# H2BR0-5.net
KiCad netlist of a schematic drawn in EAGLE
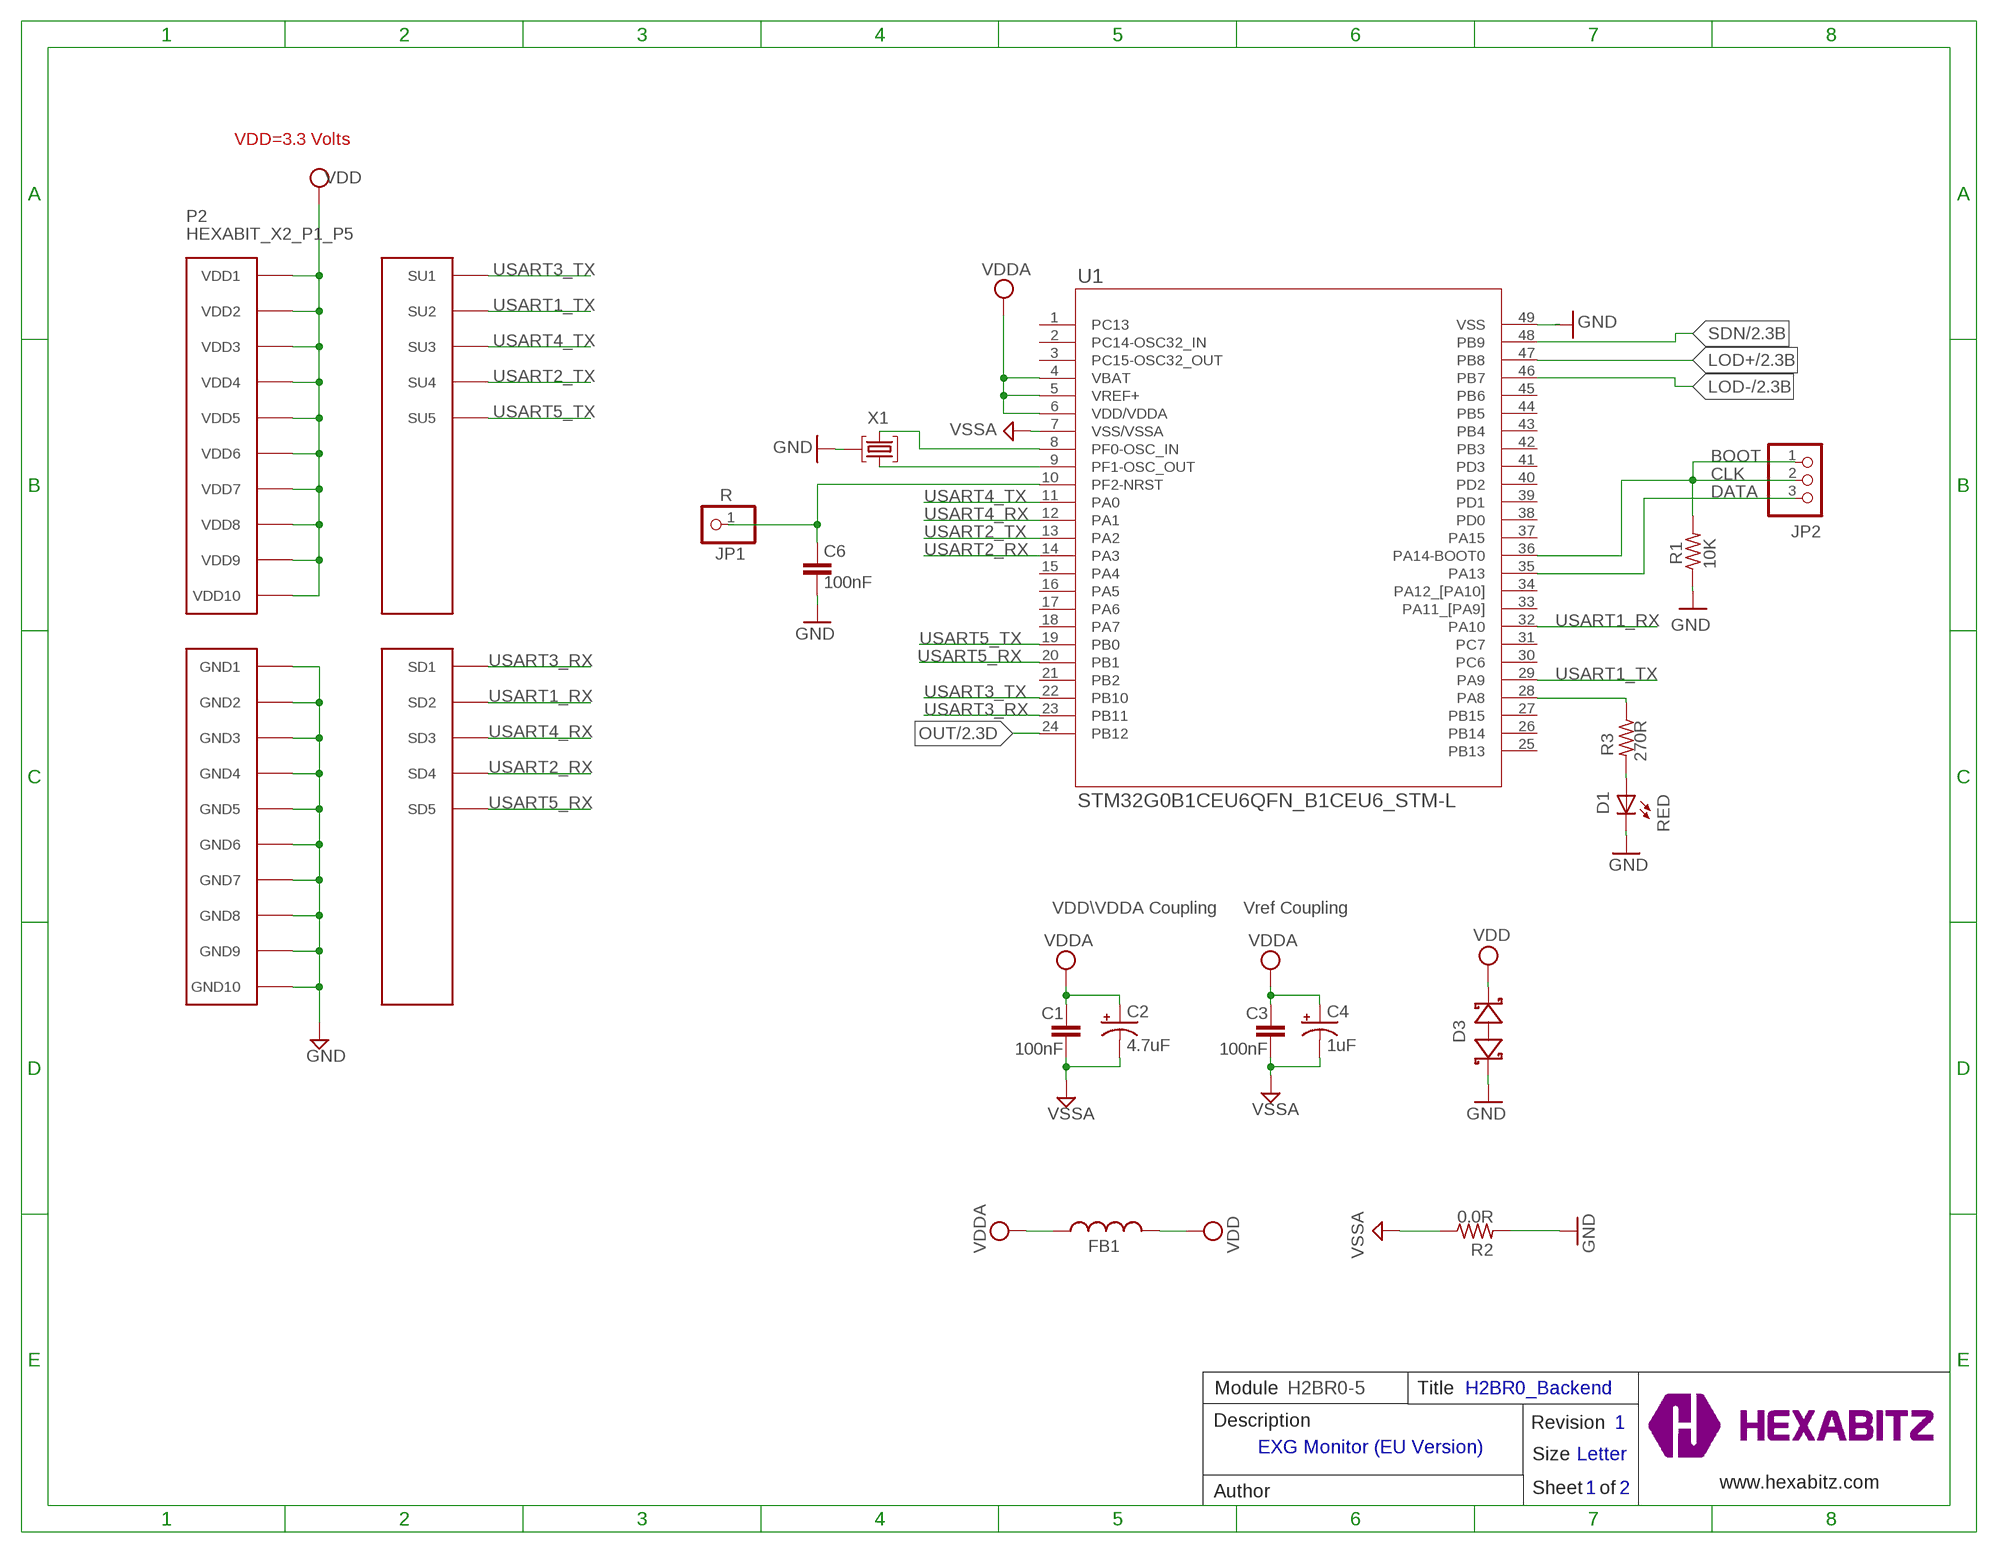
[diagram p0: schematic, sheet 1]
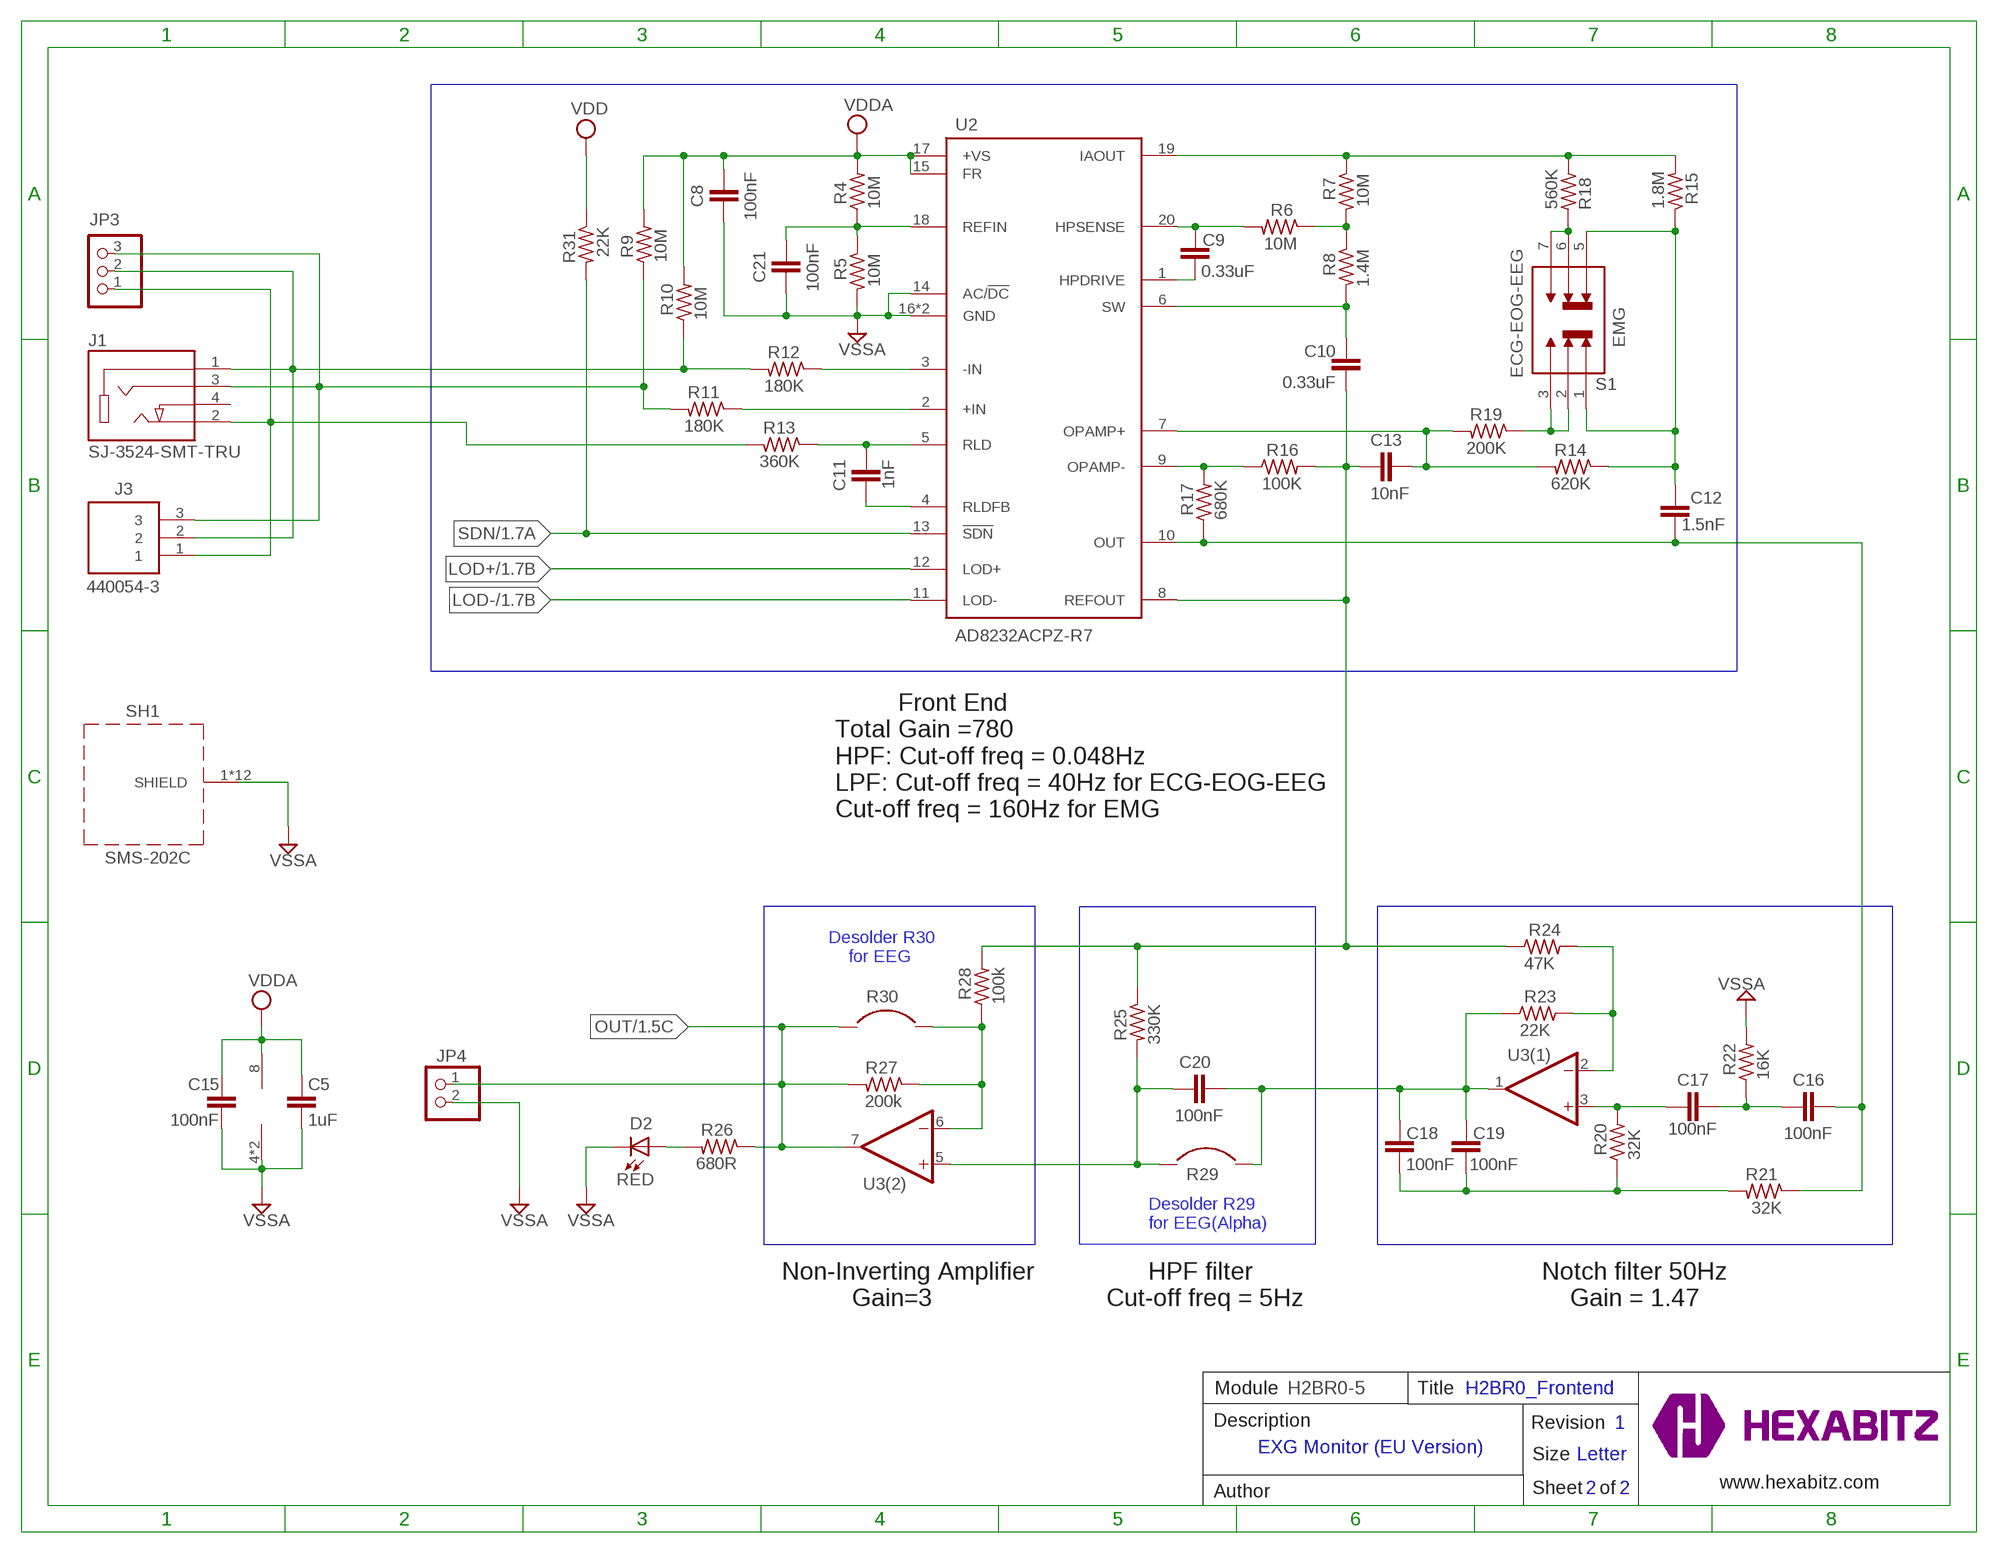
[diagram p1: schematic, sheet 2]

(export (version "E")
  (design (tool "Eeschema 10.0.6"))
  (components
    (comp (ref "C1")
      (value "100nF")
      (footprint "eagle-import:C-0603")
      (libsource (lib "eagle-import") (part "C-0603"))
    )
    (comp (ref "C2")
      (value "4.7uF")
      (footprint "eagle-import:C-0805-POL")
      (libsource (lib "eagle-import") (part "C-0805-POL"))
    )
    (comp (ref "C3")
      (value "100nF")
      (footprint "eagle-import:C-0603")
      (libsource (lib "eagle-import") (part "C-0603"))
    )
    (comp (ref "C4")
      (value "1uF")
      (footprint "eagle-import:C-0805-POL")
      (libsource (lib "eagle-import") (part "C-0805-POL"))
    )
    (comp (ref "C6")
      (value "100nF")
      (footprint "eagle-import:C-0603")
      (libsource (lib "eagle-import") (part "C-0603"))
    )
    (comp (ref "D1")
      (value "RED")
      (footprint "eagle-import:VLMS1300-GS08")
      (fields
        (field (name "MPN") "VLMS1300-GS08")
        (field (name "MFN") "Vishay")
        (field (name "MPN_1") "VLMS1300-GS08")
        (field (name "OCTOPART_URL") "https://octopart.com/vlms1300-gs08-vishay-21709201?r=sp&s=_gcP4_q8T1SC6PJQPTQ9yA")
      )
      (libsource (lib "eagle-import") (part "VLMS1300-GS08"))
    )
    (comp (ref "D3")
      (value "BOURNS_CDSOD323-T03SCBOURNS_CDSOD323-T03SC_0_0")
      (footprint "eagle-import:BOURNS_CDSOD323-T03SC_0")
      (fields (field (name "MPN") "CDSOD323-T03SC"))
      (libsource (lib "eagle-import") (part "BOURNS_CDSOD323-T03SCBOURNS_CDSOD323-T03SC_0_0"))
    )
    (comp (ref "FB1")
      (value "FB-0603")
      (footprint "eagle-import:FB-0603")
      (libsource (lib "eagle-import") (part "FB-0603"))
    )
    (comp (ref "JP1")
      (value "R")
      (footprint "eagle-import:1X01")
      (fields (field (name "MPN") "87227-1"))
      (libsource (lib "eagle-import") (part "PINHD-1X1"))
    )
    (comp (ref "JP2")
      (value "PINHD-1X3")
      (footprint "eagle-import:1X03")
      (libsource (lib "eagle-import") (part "PINHD-1X3"))
    )
    (comp (ref "P2")
      (value "HEXABIT_X2_P1_P5")
      (footprint "eagle-import:HEXABIT_17.32_X2_P1_P5")
      (libsource (lib "eagle-import") (part "HEXABIT_X2_P1_P5"))
    )
    (comp (ref "R1")
      (value "10K")
      (footprint "eagle-import:R-0603")
      (libsource (lib "eagle-import") (part "R-0603"))
    )
    (comp (ref "R2")
      (value "0.0R")
      (footprint "eagle-import:R-0603")
      (libsource (lib "eagle-import") (part "R-0603"))
    )
    (comp (ref "R3")
      (value "270R")
      (footprint "eagle-import:R-0603")
      (libsource (lib "eagle-import") (part "R-0603"))
    )
    (comp (ref "TRIMBLE-LOGO2")
      (value "HEXA-LOGO")
      (footprint "eagle-import:HEXA-LOGO")
      (libsource (lib "eagle-import") (part "HEXA-LOGO"))
    )
    (comp (ref "U1")
      (value "STM32G0B1CEU6QFN_B1CEU6_STM-L")
      (footprint "eagle-import:QFN_B1CEU6_STM-L")
      (fields
        (field (name "MANUFACTURER_PART_NUMBER") "STM32G0B1CEU6")
        (field (name "COPYRIGHT") "Copyright (C) 2021 Ultra Librarian. All rights reserved.")
      )
      (libsource (lib "eagle-import") (part "STM32G0B1CEU6QFN_B1CEU6_STM-L"))
    )
    (comp (ref "X1")
      (value "XTALL_CSTCE8M00G52")
      (footprint "eagle-import:XTALL_CSTCE8M00G52")
      (fields (field (name "MPN") "CSTCE8M00G52Z-R0"))
      (libsource (lib "eagle-import") (part "XTALL_CSTCE8M00G52"))
    )
    (comp (ref "C5")
      (value "1uF")
      (footprint "eagle-import:C-0402")
      (libsource (lib "eagle-import") (part "C-0402"))
    )
    (comp (ref "C8")
      (value "100nF")
      (footprint "eagle-import:C-0402")
      (libsource (lib "eagle-import") (part "C-0402"))
    )
    (comp (ref "C9")
      (value "0.33uF")
      (footprint "eagle-import:C-0402")
      (libsource (lib "eagle-import") (part "C-0402"))
    )
    (comp (ref "C10")
      (value "0.33uF")
      (footprint "eagle-import:C-0402")
      (libsource (lib "eagle-import") (part "C-0402"))
    )
    (comp (ref "C11")
      (value "1nF")
      (footprint "eagle-import:C-0402")
      (libsource (lib "eagle-import") (part "C-0402"))
    )
    (comp (ref "C12")
      (value "1.5nF")
      (footprint "eagle-import:C-0402")
      (libsource (lib "eagle-import") (part "C-0402"))
    )
    (comp (ref "C13")
      (value "10nF")
      (footprint "eagle-import:C-0402")
      (libsource (lib "eagle-import") (part "C-0402"))
    )
    (comp (ref "C15")
      (value "100nF")
      (footprint "eagle-import:C-0402")
      (libsource (lib "eagle-import") (part "C-0402"))
    )
    (comp (ref "C16")
      (value "100nF")
      (footprint "eagle-import:C-0402")
      (libsource (lib "eagle-import") (part "C-0402"))
    )
    (comp (ref "C17")
      (value "100nF")
      (footprint "eagle-import:C-0402")
      (libsource (lib "eagle-import") (part "C-0402"))
    )
    (comp (ref "C18")
      (value "100nF")
      (footprint "eagle-import:C-0402")
      (libsource (lib "eagle-import") (part "C-0402"))
    )
    (comp (ref "C19")
      (value "100nF")
      (footprint "eagle-import:C-0402")
      (libsource (lib "eagle-import") (part "C-0402"))
    )
    (comp (ref "C20")
      (value "100nF")
      (footprint "eagle-import:C-0402")
      (fields (field (name "MPN") "GRM188R61A105KA61J"))
      (libsource (lib "eagle-import") (part "C-0402"))
    )
    (comp (ref "C21")
      (value "100nF")
      (footprint "eagle-import:C-0402")
      (libsource (lib "eagle-import") (part "C-0402"))
    )
    (comp (ref "D2")
      (value "RED")
      (footprint "eagle-import:VLMS1300-GS08")
      (fields
        (field (name "MPN") "VLMS1300-GS08")
        (field (name "MFN") "Vishay")
        (field (name "MPN_1") "VLMS1300-GS08")
        (field (name "OCTOPART_URL") "https://octopart.com/vlms1300-gs08-vishay-21709201?r=sp&s=_gcP4_q8T1SC6PJQPTQ9yA")
      )
      (libsource (lib "eagle-import") (part "VLMS1300-GS08"))
    )
    (comp (ref "J1")
      (value "SJ-3524-SMT-TRU")
      (footprint "eagle-import:CUI_SJ-3524-SMT")
      (fields (field (name "MPN") "SJ-3524-SMT-TR"))
      (libsource (lib "eagle-import") (part "SJ-3524-SMT-TRU"))
    )
    (comp (ref "J3")
      (value "440054-3")
      (footprint "eagle-import:SHDR3W50P0X200_1X3_800X470X635")
      (fields (field (name "MOUSER_PART_NUMBER") "571-440054-3"))
      (libsource (lib "eagle-import") (part "440054-3"))
    )
    (comp (ref "JP3")
      (value "PINHD-1X3")
      (footprint "eagle-import:1X03")
      (libsource (lib "eagle-import") (part "PINHD-1X3"))
    )
    (comp (ref "JP4")
      (value "PINHD-1X2(ROUND)")
      (footprint "eagle-import:1X02")
      (libsource (lib "eagle-import") (part "PINHD-1X2(ROUND)"))
    )
    (comp (ref "R4")
      (value "10M")
      (footprint "eagle-import:R-0402")
      (libsource (lib "eagle-import") (part "R-0402"))
    )
    (comp (ref "R5")
      (value "10M")
      (footprint "eagle-import:R-0402")
      (libsource (lib "eagle-import") (part "R-0402"))
    )
    (comp (ref "R6")
      (value "10M")
      (footprint "eagle-import:R-0402")
      (libsource (lib "eagle-import") (part "R-0402"))
    )
    (comp (ref "R7")
      (value "10M")
      (footprint "eagle-import:R-0402")
      (libsource (lib "eagle-import") (part "R-0402"))
    )
    (comp (ref "R8")
      (value "1.4M")
      (footprint "eagle-import:R-0402")
      (libsource (lib "eagle-import") (part "R-0402"))
    )
    (comp (ref "R9")
      (value "10M")
      (footprint "eagle-import:R-0402")
      (libsource (lib "eagle-import") (part "R-0402"))
    )
    (comp (ref "R10")
      (value "10M")
      (footprint "eagle-import:R-0402")
      (libsource (lib "eagle-import") (part "R-0402"))
    )
    (comp (ref "R11")
      (value "180K")
      (footprint "eagle-import:R-0402")
      (libsource (lib "eagle-import") (part "R-0402"))
    )
    (comp (ref "R12")
      (value "180K")
      (footprint "eagle-import:R-0402")
      (libsource (lib "eagle-import") (part "R-0402"))
    )
    (comp (ref "R13")
      (value "360K")
      (footprint "eagle-import:R-0402")
      (libsource (lib "eagle-import") (part "R-0402"))
    )
    (comp (ref "R14")
      (value "620K")
      (footprint "eagle-import:R-0402")
      (libsource (lib "eagle-import") (part "R-0402"))
    )
    (comp (ref "R15")
      (value "1.8M")
      (footprint "eagle-import:R-0402")
      (libsource (lib "eagle-import") (part "R-0402"))
    )
    (comp (ref "R16")
      (value "100K")
      (footprint "eagle-import:R-0402")
      (libsource (lib "eagle-import") (part "R-0402"))
    )
    (comp (ref "R17")
      (value "680K")
      (footprint "eagle-import:R-0402")
      (libsource (lib "eagle-import") (part "R-0402"))
    )
    (comp (ref "R18")
      (value "560K")
      (footprint "eagle-import:R-0402")
      (libsource (lib "eagle-import") (part "R-0402"))
    )
    (comp (ref "R19")
      (value "200K")
      (footprint "eagle-import:R-0402")
      (libsource (lib "eagle-import") (part "R-0402"))
    )
    (comp (ref "R20")
      (value "32K")
      (footprint "eagle-import:R-0402")
      (libsource (lib "eagle-import") (part "R-0402"))
    )
    (comp (ref "R21")
      (value "32K")
      (footprint "eagle-import:R-0402")
      (libsource (lib "eagle-import") (part "R-0402"))
    )
    (comp (ref "R22")
      (value "16K")
      (footprint "eagle-import:R-0402")
      (libsource (lib "eagle-import") (part "R-0402"))
    )
    (comp (ref "R23")
      (value "22K")
      (footprint "eagle-import:R-0402")
      (libsource (lib "eagle-import") (part "R-0402"))
    )
    (comp (ref "R24")
      (value "47K")
      (footprint "eagle-import:R-0402")
      (libsource (lib "eagle-import") (part "R-0402"))
    )
    (comp (ref "R25")
      (value "330K")
      (footprint "eagle-import:R-0402")
      (libsource (lib "eagle-import") (part "R-0402"))
    )
    (comp (ref "R26")
      (value "680R")
      (footprint "eagle-import:R-0603")
      (libsource (lib "eagle-import") (part "R-0603"))
    )
    (comp (ref "R27")
      (value "200k")
      (footprint "eagle-import:R-0402")
      (libsource (lib "eagle-import") (part "R-0402"))
    )
    (comp (ref "R28")
      (value "100k")
      (footprint "eagle-import:R-0402")
      (libsource (lib "eagle-import") (part "R-0402"))
    )
    (comp (ref "R29")
      (value "SB-0603")
      (footprint "eagle-import:SB-0603")
      (libsource (lib "eagle-import") (part "SB-0603"))
    )
    (comp (ref "R30")
      (value "SB-0603")
      (footprint "eagle-import:SB-0603")
      (libsource (lib "eagle-import") (part "SB-0603"))
    )
    (comp (ref "R31")
      (value "22K")
      (footprint "eagle-import:R-0402")
      (libsource (lib "eagle-import") (part "R-0402"))
    )
    (comp (ref "S1")
      (value "JS202011JCQN")
      (footprint "eagle-import:SW_JS202011JCQN")
      (fields (field (name "MF") "C&K"))
      (libsource (lib "eagle-import") (part "JS202011JCQN"))
    )
    (comp (ref "SH1")
      (value "SMS-202C")
      (footprint "eagle-import:SMS202F")
      (fields (field (name "MOUSER_PART_NUMBER") "861-SMS-202C"))
      (libsource (lib "eagle-import") (part "SMS-202C"))
    )
    (comp (ref "U2")
      (value "AD8232ACPZ-R7")
      (footprint "eagle-import:QFN50P400X400X80-21N")
      (fields (field (name "MOUSER_PART_NUMBER") "584-AD8232ACPZ-R7"))
      (libsource (lib "eagle-import") (part "AD8232ACPZ-R7"))
    )
    (comp (ref "U3")
      (value "TSV772IQ2T_SEPARATED_SYMBOLSSON50P200X200X60-9N")
      (footprint "eagle-import:SON50P200X200X60-9N")
      (libsource (lib "eagle-import") (part "TSV772IQ2T_SEPARATED_SYMBOLSSON50P200X200X60-9N"))
    )
  )
  (nets
    (net (code "1") (name "CLK") (class "Default")
      (node (ref "JP2") (pin "1") (pinfunction "1_1") (pintype "passive"))
      (node (ref "JP2") (pin "2") (pinfunction "2_2") (pintype "passive"))
      (node (ref "R1") (pin "2") (pinfunction "2_2") (pintype "passive"))
      (node (ref "U1") (pin "36") (pinfunction "PA14-BOOT0_36") (pintype "bidirectional"))
    )
    (net (code "2") (name "DATA") (class "Default")
      (node (ref "JP2") (pin "3") (pinfunction "3_3") (pintype "passive"))
      (node (ref "U1") (pin "35") (pinfunction "PA13_35") (pintype "bidirectional"))
    )
    (net (code "3") (name "GND") (class "Default")
      (node (ref "C6") (pin "2") (pinfunction "2_2") (pintype "passive"))
      (node (ref "D1") (pin "C") (pinfunction "C_C") (pintype "passive"))
      (node (ref "D3") (pin "1") (pinfunction "A_1") (pintype "passive"))
      (node (ref "P2") (pin "PAD_PD11") (pinfunction "GND1_PAD_PD11") (pintype "power_in"))
      (node (ref "P2") (pin "PAD_PD12") (pinfunction "GND2_PAD_PD12") (pintype "power_in"))
      (node (ref "P2") (pin "PAD_PD13") (pinfunction "GND3_PAD_PD13") (pintype "power_in"))
      (node (ref "P2") (pin "PAD_PD14") (pinfunction "GND4_PAD_PD14") (pintype "power_in"))
      (node (ref "P2") (pin "PAD_PD15") (pinfunction "GND5_PAD_PD15") (pintype "power_in"))
      (node (ref "P2") (pin "PAD_PD16") (pinfunction "GND6_PAD_PD16") (pintype "power_in"))
      (node (ref "P2") (pin "PAD_PD17") (pinfunction "GND7_PAD_PD17") (pintype "power_in"))
      (node (ref "P2") (pin "PAD_PD18") (pinfunction "GND8_PAD_PD18") (pintype "power_in"))
      (node (ref "P2") (pin "PAD_PD19") (pinfunction "GND9_PAD_PD19") (pintype "power_in"))
      (node (ref "P2") (pin "PAD_PD20") (pinfunction "GND10_PAD_PD20") (pintype "power_in"))
      (node (ref "R1") (pin "1") (pinfunction "1_1") (pintype "passive"))
      (node (ref "R2") (pin "2") (pinfunction "2_2") (pintype "passive"))
      (node (ref "U1") (pin "49") (pinfunction "VSS_49") (pintype "passive"))
      (node (ref "X1") (pin "P$2") (pinfunction "2_P$2") (pintype "passive"))
    )
    (net (code "4") (name "LOD+") (class "Default")
      (node (ref "U1") (pin "47") (pinfunction "PB8_47") (pintype "bidirectional"))
      (node (ref "U2") (pin "12") (pinfunction "LOD+_12") (pintype "bidirectional"))
    )
    (net (code "5") (name "LOD-") (class "Default")
      (node (ref "U1") (pin "46") (pinfunction "PB7_46") (pintype "bidirectional"))
      (node (ref "U2") (pin "11") (pinfunction "LOD-_11") (pintype "bidirectional"))
    )
    (net (code "6") (name "Net-(C12-Pad2)") (class "Default")
      (node (ref "C12") (pin "2") (pinfunction "2_2") (pintype "passive"))
      (node (ref "R14") (pin "1") (pinfunction "1_1") (pintype "passive"))
      (node (ref "R15") (pin "1") (pinfunction "1_1") (pintype "passive"))
      (node (ref "S1") (pin "1") (pinfunction "1_1") (pintype "passive"))
      (node (ref "S1") (pin "5") (pinfunction "5_5") (pintype "passive"))
    )
    (net (code "7") (name "Net-(C16-Pad1)") (class "Default")
      (node (ref "C16") (pin "1") (pinfunction "1_1") (pintype "passive"))
      (node (ref "C17") (pin "2") (pinfunction "2_2") (pintype "passive"))
      (node (ref "R22") (pin "1") (pinfunction "1_1") (pintype "passive"))
    )
    (net (code "8") (name "Net-(C18-Pad1)") (class "Default")
      (node (ref "C18") (pin "1") (pinfunction "1_1") (pintype "passive"))
      (node (ref "C19") (pin "1") (pinfunction "1_1") (pintype "passive"))
      (node (ref "R20") (pin "1") (pinfunction "1_1") (pintype "passive"))
      (node (ref "R21") (pin "2") (pinfunction "2_2") (pintype "passive"))
    )
    (net (code "9") (name "Net-(D1-PadA)") (class "Default")
      (node (ref "D1") (pin "A") (pinfunction "A_A") (pintype "passive"))
      (node (ref "R3") (pin "2") (pinfunction "2_2") (pintype "passive"))
    )
    (net (code "10") (name "Net-(D2-PadA)") (class "Default")
      (node (ref "D2") (pin "A") (pinfunction "A_A") (pintype "passive"))
      (node (ref "R26") (pin "2") (pinfunction "2_2") (pintype "passive"))
    )
    (net (code "11") (name "Net-(J1-Pad1)") (class "Default")
      (node (ref "J1") (pin "1") (pinfunction "1_1") (pintype "passive"))
      (node (ref "J3") (pin "2") (pinfunction "2_2") (pintype "bidirectional"))
      (node (ref "JP3") (pin "2") (pinfunction "2_2") (pintype "passive"))
      (node (ref "R10") (pin "1") (pinfunction "1_1") (pintype "passive"))
      (node (ref "R12") (pin "2") (pinfunction "2_2") (pintype "passive"))
    )
    (net (code "12") (name "Net-(J1-Pad2)") (class "Default")
      (node (ref "J1") (pin "2") (pinfunction "2_2") (pintype "passive"))
      (node (ref "J3") (pin "1") (pinfunction "1_1") (pintype "bidirectional"))
      (node (ref "JP3") (pin "1") (pinfunction "1_1") (pintype "passive"))
      (node (ref "R13") (pin "2") (pinfunction "2_2") (pintype "passive"))
    )
    (net (code "13") (name "Net-(J1-Pad3)") (class "Default")
      (node (ref "J1") (pin "3") (pinfunction "3_3") (pintype "passive"))
      (node (ref "J3") (pin "3") (pinfunction "3_3") (pintype "bidirectional"))
      (node (ref "JP3") (pin "3") (pinfunction "3_3") (pintype "passive"))
      (node (ref "R11") (pin "2") (pinfunction "2_2") (pintype "passive"))
      (node (ref "R9") (pin "1") (pinfunction "1_1") (pintype "passive"))
    )
    (net (code "14") (name "Net-(R6-Pad1)") (class "Default")
      (node (ref "R6") (pin "1") (pinfunction "1_1") (pintype "passive"))
      (node (ref "R7") (pin "2") (pinfunction "2_2") (pintype "passive"))
      (node (ref "R8") (pin "1") (pinfunction "1_1") (pintype "passive"))
    )
    (net (code "15") (name "Net-(R18-Pad2)") (class "Default")
      (node (ref "R18") (pin "2") (pinfunction "2_2") (pintype "passive"))
      (node (ref "S1") (pin "6") (pinfunction "6_6") (pintype "passive"))
      (node (ref "S1") (pin "7") (pinfunction "7_7") (pintype "passive"))
    )
    (net (code "16") (name "Net-(R19-Pad1)") (class "Default")
      (node (ref "R19") (pin "1") (pinfunction "1_1") (pintype "passive"))
      (node (ref "S1") (pin "2") (pinfunction "2_2") (pintype "passive"))
      (node (ref "S1") (pin "3") (pinfunction "3_3") (pintype "passive"))
    )
    (net (code "17") (name "Net-(U1-PA8)") (class "Default")
      (node (ref "R3") (pin "1") (pinfunction "1_1") (pintype "passive"))
      (node (ref "U1") (pin "28") (pinfunction "PA8_28") (pintype "bidirectional"))
    )
    (net (code "18") (name "Net-(U1-PF0-OSC_IN)") (class "Default")
      (node (ref "U1") (pin "8") (pinfunction "PF0-OSC_IN_8") (pintype "bidirectional"))
      (node (ref "X1") (pin "P$3") (pinfunction "3_P$3") (pintype "passive"))
    )
    (net (code "19") (name "Net-(U1-PF1-OSC_OUT)") (class "Default")
      (node (ref "U1") (pin "9") (pinfunction "PF1-OSC_OUT_9") (pintype "output"))
      (node (ref "X1") (pin "P$1") (pinfunction "1_P$1") (pintype "passive"))
    )
    (net (code "20") (name "Net-(U1-PF2-NRST)") (class "Default")
      (node (ref "C6") (pin "1") (pinfunction "1_1") (pintype "passive"))
      (node (ref "JP1") (pin "1") (pinfunction "1_1") (pintype "passive"))
      (node (ref "U1") (pin "10") (pinfunction "PF2-NRST_10") (pintype "bidirectional"))
    )
    (net (code "21") (name "Net-(U2-+IN)") (class "Default")
      (node (ref "R11") (pin "1") (pinfunction "1_1") (pintype "passive"))
      (node (ref "U2") (pin "2") (pinfunction "+IN_2") (pintype "bidirectional"))
    )
    (net (code "22") (name "Net-(U2--IN)") (class "Default")
      (node (ref "R12") (pin "1") (pinfunction "1_1") (pintype "passive"))
      (node (ref "U2") (pin "3") (pinfunction "-IN_3") (pintype "bidirectional"))
    )
    (net (code "23") (name "Net-(U2-HPDRIVE)") (class "Default")
      (node (ref "C9") (pin "2") (pinfunction "2_2") (pintype "passive"))
      (node (ref "U2") (pin "1") (pinfunction "HPDRIVE_1") (pintype "bidirectional"))
    )
    (net (code "24") (name "Net-(U2-HPSENSE)") (class "Default")
      (node (ref "C9") (pin "1") (pinfunction "1_1") (pintype "passive"))
      (node (ref "R6") (pin "2") (pinfunction "2_2") (pintype "passive"))
      (node (ref "U2") (pin "20") (pinfunction "HPSENSE_20") (pintype "bidirectional"))
    )
    (net (code "25") (name "Net-(U2-IAOUT)") (class "Default")
      (node (ref "R15") (pin "2") (pinfunction "2_2") (pintype "passive"))
      (node (ref "R18") (pin "1") (pinfunction "1_1") (pintype "passive"))
      (node (ref "R7") (pin "1") (pinfunction "1_1") (pintype "passive"))
      (node (ref "U2") (pin "19") (pinfunction "IAOUT_19") (pintype "bidirectional"))
    )
    (net (code "26") (name "Net-(U2-OPAMP+)") (class "Default")
      (node (ref "C13") (pin "1") (pinfunction "1_1") (pintype "passive"))
      (node (ref "R14") (pin "2") (pinfunction "2_2") (pintype "passive"))
      (node (ref "R19") (pin "2") (pinfunction "2_2") (pintype "passive"))
      (node (ref "U2") (pin "7") (pinfunction "OPAMP+_7") (pintype "bidirectional"))
    )
    (net (code "27") (name "Net-(U2-OPAMP-)") (class "Default")
      (node (ref "R16") (pin "1") (pinfunction "1_1") (pintype "passive"))
      (node (ref "R17") (pin "2") (pinfunction "2_2") (pintype "passive"))
      (node (ref "U2") (pin "9") (pinfunction "OPAMP-_9") (pintype "bidirectional"))
    )
    (net (code "28") (name "Net-(U2-OUT)") (class "Default")
      (node (ref "C12") (pin "1") (pinfunction "1_1") (pintype "passive"))
      (node (ref "C16") (pin "2") (pinfunction "2_2") (pintype "passive"))
      (node (ref "R17") (pin "1") (pinfunction "1_1") (pintype "passive"))
      (node (ref "R21") (pin "1") (pinfunction "1_1") (pintype "passive"))
      (node (ref "U2") (pin "10") (pinfunction "OUT_10") (pintype "bidirectional"))
    )
    (net (code "29") (name "Net-(U2-REFIN)") (class "Default")
      (node (ref "C21") (pin "1") (pinfunction "1_1") (pintype "passive"))
      (node (ref "R4") (pin "1") (pinfunction "1_1") (pintype "passive"))
      (node (ref "R5") (pin "1") (pinfunction "1_1") (pintype "passive"))
      (node (ref "U2") (pin "18") (pinfunction "REFIN_18") (pintype "bidirectional"))
    )
    (net (code "30") (name "Net-(U2-REFOUT)") (class "Default")
      (node (ref "C10") (pin "2") (pinfunction "2_2") (pintype "passive"))
      (node (ref "C13") (pin "2") (pinfunction "2_2") (pintype "passive"))
      (node (ref "R16") (pin "2") (pinfunction "2_2") (pintype "passive"))
      (node (ref "R24") (pin "1") (pinfunction "1_1") (pintype "passive"))
      (node (ref "R25") (pin "1") (pinfunction "1_1") (pintype "passive"))
      (node (ref "R28") (pin "2") (pinfunction "2_2") (pintype "passive"))
      (node (ref "U2") (pin "8") (pinfunction "REFOUT_8") (pintype "bidirectional"))
    )
    (net (code "31") (name "Net-(U2-RLD)") (class "Default")
      (node (ref "C11") (pin "1") (pinfunction "1_1") (pintype "passive"))
      (node (ref "R13") (pin "1") (pinfunction "1_1") (pintype "passive"))
      (node (ref "U2") (pin "5") (pinfunction "RLD_5") (pintype "bidirectional"))
    )
    (net (code "32") (name "Net-(U2-RLDFB)") (class "Default")
      (node (ref "C11") (pin "2") (pinfunction "2_2") (pintype "passive"))
      (node (ref "U2") (pin "4") (pinfunction "RLDFB_4") (pintype "bidirectional"))
    )
    (net (code "33") (name "Net-(U2-SW)") (class "Default")
      (node (ref "C10") (pin "1") (pinfunction "1_1") (pintype "passive"))
      (node (ref "R8") (pin "2") (pinfunction "2_2") (pintype "passive"))
      (node (ref "U2") (pin "6") (pinfunction "SW_6") (pintype "bidirectional"))
    )
    (net (code "34") (name "Net-(U3A-+IN)") (class "Default")
      (node (ref "C17") (pin "1") (pinfunction "1_1") (pintype "passive"))
      (node (ref "R20") (pin "2") (pinfunction "2_2") (pintype "passive"))
      (node (ref "U3") (pin "3") (pinfunction "+IN_3") (pintype "input"))
    )
    (net (code "35") (name "Net-(U3A--IN)") (class "Default")
      (node (ref "R23") (pin "2") (pinfunction "2_2") (pintype "passive"))
      (node (ref "R24") (pin "2") (pinfunction "2_2") (pintype "passive"))
      (node (ref "U3") (pin "2") (pinfunction "-IN_2") (pintype "input"))
    )
    (net (code "36") (name "Net-(U3A-OUT)") (class "Default")
      (node (ref "C18") (pin "2") (pinfunction "2_2") (pintype "passive"))
      (node (ref "C19") (pin "2") (pinfunction "2_2") (pintype "passive"))
      (node (ref "C20") (pin "2") (pinfunction "2_2") (pintype "passive"))
      (node (ref "R23") (pin "1") (pinfunction "1_1") (pintype "passive"))
      (node (ref "R29") (pin "2") (pinfunction "2_2") (pintype "passive"))
      (node (ref "U3") (pin "1") (pinfunction "OUT_1") (pintype "output"))
    )
    (net (code "37") (name "Net-(U3B-+IN)") (class "Default")
      (node (ref "C20") (pin "1") (pinfunction "1_1") (pintype "passive"))
      (node (ref "R25") (pin "2") (pinfunction "2_2") (pintype "passive"))
      (node (ref "R29") (pin "1") (pinfunction "1_1") (pintype "passive"))
      (node (ref "U3") (pin "5") (pinfunction "+IN_5") (pintype "input"))
    )
    (net (code "38") (name "Net-(U3B--IN)") (class "Default")
      (node (ref "R27") (pin "1") (pinfunction "1_1") (pintype "passive"))
      (node (ref "R28") (pin "1") (pinfunction "1_1") (pintype "passive"))
      (node (ref "R30") (pin "2") (pinfunction "2_2") (pintype "passive"))
      (node (ref "U3") (pin "6") (pinfunction "-IN_6") (pintype "input"))
    )
    (net (code "39") (name "OUT") (class "Default")
      (node (ref "JP4") (pin "1") (pinfunction "1_1") (pintype "passive"))
      (node (ref "R26") (pin "1") (pinfunction "1_1") (pintype "passive"))
      (node (ref "R27") (pin "2") (pinfunction "2_2") (pintype "passive"))
      (node (ref "R30") (pin "1") (pinfunction "1_1") (pintype "passive"))
      (node (ref "U1") (pin "24") (pinfunction "PB12_24") (pintype "bidirectional"))
      (node (ref "U3") (pin "7") (pinfunction "OUT_7") (pintype "output"))
    )
    (net (code "40") (name "SDN") (class "Default")
      (node (ref "R31") (pin "2") (pinfunction "2_2") (pintype "passive"))
      (node (ref "U1") (pin "48") (pinfunction "PB9_48") (pintype "bidirectional"))
      (node (ref "U2") (pin "13") (pinfunction "~{SDN}_13") (pintype "bidirectional"))
    )
    (net (code "41") (name "USART1_RX") (class "Default")
      (node (ref "P2") (pin "PAD_PD2") (pinfunction "SD2_PAD_PD2") (pintype "bidirectional"))
      (node (ref "U1") (pin "32") (pinfunction "PA10_32") (pintype "bidirectional"))
    )
    (net (code "42") (name "USART1_TX") (class "Default")
      (node (ref "P2") (pin "PAD_PU2") (pinfunction "SU2_PAD_PU2") (pintype "bidirectional"))
      (node (ref "U1") (pin "29") (pinfunction "PA9_29") (pintype "bidirectional"))
    )
    (net (code "43") (name "USART2_RX") (class "Default")
      (node (ref "P2") (pin "PAD_PD4") (pinfunction "SD4_PAD_PD4") (pintype "bidirectional"))
      (node (ref "U1") (pin "14") (pinfunction "PA3_14") (pintype "bidirectional"))
    )
    (net (code "44") (name "USART2_TX") (class "Default")
      (node (ref "P2") (pin "PAD_PU4") (pinfunction "SU4_PAD_PU4") (pintype "bidirectional"))
      (node (ref "U1") (pin "13") (pinfunction "PA2_13") (pintype "bidirectional"))
    )
    (net (code "45") (name "USART3_RX") (class "Default")
      (node (ref "P2") (pin "PAD_PD1") (pinfunction "SD1_PAD_PD1") (pintype "bidirectional"))
      (node (ref "U1") (pin "23") (pinfunction "PB11_23") (pintype "bidirectional"))
    )
    (net (code "46") (name "USART3_TX") (class "Default")
      (node (ref "P2") (pin "PAD_PU1") (pinfunction "SU1_PAD_PU1") (pintype "bidirectional"))
      (node (ref "U1") (pin "22") (pinfunction "PB10_22") (pintype "bidirectional"))
    )
    (net (code "47") (name "USART4_RX") (class "Default")
      (node (ref "P2") (pin "PAD_PD3") (pinfunction "SD3_PAD_PD3") (pintype "bidirectional"))
      (node (ref "U1") (pin "12") (pinfunction "PA1_12") (pintype "bidirectional"))
    )
    (net (code "48") (name "USART4_TX") (class "Default")
      (node (ref "P2") (pin "PAD_PU3") (pinfunction "SU3_PAD_PU3") (pintype "bidirectional"))
      (node (ref "U1") (pin "11") (pinfunction "PA0_11") (pintype "bidirectional"))
    )
    (net (code "49") (name "USART5_RX") (class "Default")
      (node (ref "P2") (pin "PAD_PD5") (pinfunction "SD5_PAD_PD5") (pintype "bidirectional"))
      (node (ref "U1") (pin "20") (pinfunction "PB1_20") (pintype "bidirectional"))
    )
    (net (code "50") (name "USART5_TX") (class "Default")
      (node (ref "P2") (pin "PAD_PU5") (pinfunction "SU5_PAD_PU5") (pintype "bidirectional"))
      (node (ref "U1") (pin "19") (pinfunction "PB0_19") (pintype "bidirectional"))
    )
    (net (code "51") (name "VDD") (class "Default")
      (node (ref "D3") (pin "2") (pinfunction "C_2") (pintype "passive"))
      (node (ref "FB1") (pin "2") (pinfunction "2_2") (pintype "passive"))
      (node (ref "P2") (pin "PAD_PU11") (pinfunction "VDD1_PAD_PU11") (pintype "power_in"))
      (node (ref "P2") (pin "PAD_PU12") (pinfunction "VDD2_PAD_PU12") (pintype "power_in"))
      (node (ref "P2") (pin "PAD_PU13") (pinfunction "VDD3_PAD_PU13") (pintype "power_in"))
      (node (ref "P2") (pin "PAD_PU14") (pinfunction "VDD4_PAD_PU14") (pintype "power_in"))
      (node (ref "P2") (pin "PAD_PU15") (pinfunction "VDD5_PAD_PU15") (pintype "power_in"))
      (node (ref "P2") (pin "PAD_PU16") (pinfunction "VDD6_PAD_PU16") (pintype "power_in"))
      (node (ref "P2") (pin "PAD_PU17") (pinfunction "VDD7_PAD_PU17") (pintype "power_in"))
      (node (ref "P2") (pin "PAD_PU18") (pinfunction "VDD8_PAD_PU18") (pintype "power_in"))
      (node (ref "P2") (pin "PAD_PU19") (pinfunction "VDD9_PAD_PU19") (pintype "power_in"))
      (node (ref "P2") (pin "PAD_PU20") (pinfunction "VDD10_PAD_PU20") (pintype "power_in"))
      (node (ref "R31") (pin "1") (pinfunction "1_1") (pintype "passive"))
    )
    (net (code "52") (name "VDDA") (class "Default")
      (node (ref "C1") (pin "1") (pinfunction "1_1") (pintype "passive"))
      (node (ref "C15") (pin "1") (pinfunction "1_1") (pintype "passive"))
      (node (ref "C2") (pin "1") (pinfunction "+_1") (pintype "passive"))
      (node (ref "C3") (pin "1") (pinfunction "1_1") (pintype "passive"))
      (node (ref "C4") (pin "1") (pinfunction "+_1") (pintype "passive"))
      (node (ref "C5") (pin "1") (pinfunction "1_1") (pintype "passive"))
      (node (ref "C8") (pin "1") (pinfunction "1_1") (pintype "passive"))
      (node (ref "FB1") (pin "1") (pinfunction "1_1") (pintype "passive"))
      (node (ref "R10") (pin "2") (pinfunction "2_2") (pintype "passive"))
      (node (ref "R4") (pin "2") (pinfunction "2_2") (pintype "passive"))
      (node (ref "R9") (pin "2") (pinfunction "2_2") (pintype "passive"))
      (node (ref "U1") (pin "4") (pinfunction "VBAT_4") (pintype "passive"))
      (node (ref "U1") (pin "5") (pinfunction "VREF+_5") (pintype "power_in"))
      (node (ref "U1") (pin "6") (pinfunction "VDD/VDDA_6") (pintype "power_in"))
      (node (ref "U2") (pin "15") (pinfunction "FR_15") (pintype "bidirectional"))
      (node (ref "U2") (pin "17") (pinfunction "+VS_17") (pintype "bidirectional"))
      (node (ref "U3") (pin "8") (pinfunction "V+_8") (pintype "power_in"))
    )
    (net (code "53") (name "VSSA") (class "Default")
      (node (ref "C1") (pin "2") (pinfunction "2_2") (pintype "passive"))
      (node (ref "C15") (pin "2") (pinfunction "2_2") (pintype "passive"))
      (node (ref "C2") (pin "2") (pinfunction "-_2") (pintype "passive"))
      (node (ref "C21") (pin "2") (pinfunction "2_2") (pintype "passive"))
      (node (ref "C3") (pin "2") (pinfunction "2_2") (pintype "passive"))
      (node (ref "C4") (pin "2") (pinfunction "-_2") (pintype "passive"))
      (node (ref "C5") (pin "2") (pinfunction "2_2") (pintype "passive"))
      (node (ref "C8") (pin "2") (pinfunction "2_2") (pintype "passive"))
      (node (ref "D2") (pin "C") (pinfunction "C_C") (pintype "passive"))
      (node (ref "JP4") (pin "2") (pinfunction "2_2") (pintype "passive"))
      (node (ref "R2") (pin "1") (pinfunction "1_1") (pintype "passive"))
      (node (ref "R22") (pin "2") (pinfunction "2_2") (pintype "passive"))
      (node (ref "R5") (pin "2") (pinfunction "2_2") (pintype "passive"))
      (node (ref "SH1") (pin "1") (pinfunction "SHIELD_1") (pintype "bidirectional"))
      (node (ref "SH1") (pin "10") (pinfunction "SHIELD_10") (pintype "bidirectional"))
      (node (ref "SH1") (pin "11") (pinfunction "SHIELD_11") (pintype "bidirectional"))
      (node (ref "SH1") (pin "12") (pinfunction "SHIELD_12") (pintype "bidirectional"))
      (node (ref "SH1") (pin "2") (pinfunction "SHIELD_2") (pintype "bidirectional"))
      (node (ref "SH1") (pin "3") (pinfunction "SHIELD_3") (pintype "bidirectional"))
      (node (ref "SH1") (pin "4") (pinfunction "SHIELD_4") (pintype "bidirectional"))
      (node (ref "SH1") (pin "5") (pinfunction "SHIELD_5") (pintype "bidirectional"))
      (node (ref "SH1") (pin "6") (pinfunction "SHIELD_6") (pintype "bidirectional"))
      (node (ref "SH1") (pin "7") (pinfunction "SHIELD_7") (pintype "bidirectional"))
      (node (ref "SH1") (pin "8") (pinfunction "SHIELD_8") (pintype "bidirectional"))
      (node (ref "SH1") (pin "9") (pinfunction "SHIELD_9") (pintype "bidirectional"))
      (node (ref "U1") (pin "7") (pinfunction "VSS/VSSA_7") (pintype "passive"))
      (node (ref "U2") (pin "14") (pinfunction "AC/~{DC}_14") (pintype "bidirectional"))
      (node (ref "U2") (pin "16") (pinfunction "GND_16") (pintype "bidirectional"))
      (node (ref "U2") (pin "21") (pinfunction "GND_21") (pintype "bidirectional"))
      (node (ref "U3") (pin "4") (pinfunction "V-_4") (pintype "power_in"))
      (node (ref "U3") (pin "9") (pinfunction "V-_9") (pintype "power_in"))
    )
    (net (code "54") (name "unconnected-(J1-Pad4)") (class "Default")
      (node (ref "J1") (pin "4") (pinfunction "4_4") (pintype "passive"))
    )
    (net (code "55") (name "unconnected-(U1-PA4-Pad15)") (class "Default")
      (node (ref "U1") (pin "15") (pinfunction "PA4_15") (pintype "bidirectional"))
    )
    (net (code "56") (name "unconnected-(U1-PA5-Pad16)") (class "Default")
      (node (ref "U1") (pin "16") (pinfunction "PA5_16") (pintype "bidirectional"))
    )
    (net (code "57") (name "unconnected-(U1-PA6-Pad17)") (class "Default")
      (node (ref "U1") (pin "17") (pinfunction "PA6_17") (pintype "bidirectional"))
    )
    (net (code "58") (name "unconnected-(U1-PA7-Pad18)") (class "Default")
      (node (ref "U1") (pin "18") (pinfunction "PA7_18") (pintype "bidirectional"))
    )
    (net (code "59") (name "unconnected-(U1-PA11_[PA9]-Pad33)") (class "Default")
      (node (ref "U1") (pin "33") (pinfunction "PA11_[PA9]_33") (pintype "bidirectional"))
    )
    (net (code "60") (name "unconnected-(U1-PA12_[PA10]-Pad34)") (class "Default")
      (node (ref "U1") (pin "34") (pinfunction "PA12_[PA10]_34") (pintype "bidirectional"))
    )
    (net (code "61") (name "unconnected-(U1-PA15-Pad37)") (class "Default")
      (node (ref "U1") (pin "37") (pinfunction "PA15_37") (pintype "bidirectional"))
    )
    (net (code "62") (name "unconnected-(U1-PB2-Pad21)") (class "Default")
      (node (ref "U1") (pin "21") (pinfunction "PB2_21") (pintype "bidirectional"))
    )
    (net (code "63") (name "unconnected-(U1-PB3-Pad42)") (class "Default")
      (node (ref "U1") (pin "42") (pinfunction "PB3_42") (pintype "bidirectional"))
    )
    (net (code "64") (name "unconnected-(U1-PB4-Pad43)") (class "Default")
      (node (ref "U1") (pin "43") (pinfunction "PB4_43") (pintype "bidirectional"))
    )
    (net (code "65") (name "unconnected-(U1-PB5-Pad44)") (class "Default")
      (node (ref "U1") (pin "44") (pinfunction "PB5_44") (pintype "bidirectional"))
    )
    (net (code "66") (name "unconnected-(U1-PB6-Pad45)") (class "Default")
      (node (ref "U1") (pin "45") (pinfunction "PB6_45") (pintype "bidirectional"))
    )
    (net (code "67") (name "unconnected-(U1-PB13-Pad25)") (class "Default")
      (node (ref "U1") (pin "25") (pinfunction "PB13_25") (pintype "bidirectional"))
    )
    (net (code "68") (name "unconnected-(U1-PB14-Pad26)") (class "Default")
      (node (ref "U1") (pin "26") (pinfunction "PB14_26") (pintype "bidirectional"))
    )
    (net (code "69") (name "unconnected-(U1-PB15-Pad27)") (class "Default")
      (node (ref "U1") (pin "27") (pinfunction "PB15_27") (pintype "bidirectional"))
    )
    (net (code "70") (name "unconnected-(U1-PC6-Pad30)") (class "Default")
      (node (ref "U1") (pin "30") (pinfunction "PC6_30") (pintype "bidirectional"))
    )
    (net (code "71") (name "unconnected-(U1-PC7-Pad31)") (class "Default")
      (node (ref "U1") (pin "31") (pinfunction "PC7_31") (pintype "bidirectional"))
    )
    (net (code "72") (name "unconnected-(U1-PC13-Pad1)") (class "Default")
      (node (ref "U1") (pin "1") (pinfunction "PC13_1") (pintype "bidirectional"))
    )
    (net (code "73") (name "unconnected-(U1-PC14-OSC32_IN-Pad2)") (class "Default")
      (node (ref "U1") (pin "2") (pinfunction "PC14-OSC32_IN_2") (pintype "bidirectional"))
    )
    (net (code "74") (name "unconnected-(U1-PC15-OSC32_OUT-Pad3)") (class "Default")
      (node (ref "U1") (pin "3") (pinfunction "PC15-OSC32_OUT_3") (pintype "output"))
    )
    (net (code "75") (name "unconnected-(U1-PD0-Pad38)") (class "Default")
      (node (ref "U1") (pin "38") (pinfunction "PD0_38") (pintype "bidirectional"))
    )
    (net (code "76") (name "unconnected-(U1-PD1-Pad39)") (class "Default")
      (node (ref "U1") (pin "39") (pinfunction "PD1_39") (pintype "bidirectional"))
    )
    (net (code "77") (name "unconnected-(U1-PD2-Pad40)") (class "Default")
      (node (ref "U1") (pin "40") (pinfunction "PD2_40") (pintype "bidirectional"))
    )
    (net (code "78") (name "unconnected-(U1-PD3-Pad41)") (class "Default")
      (node (ref "U1") (pin "41") (pinfunction "PD3_41") (pintype "bidirectional"))
    )
  )
)
